# H32R10.net
KiCad netlist of a schematic drawn in EAGLE
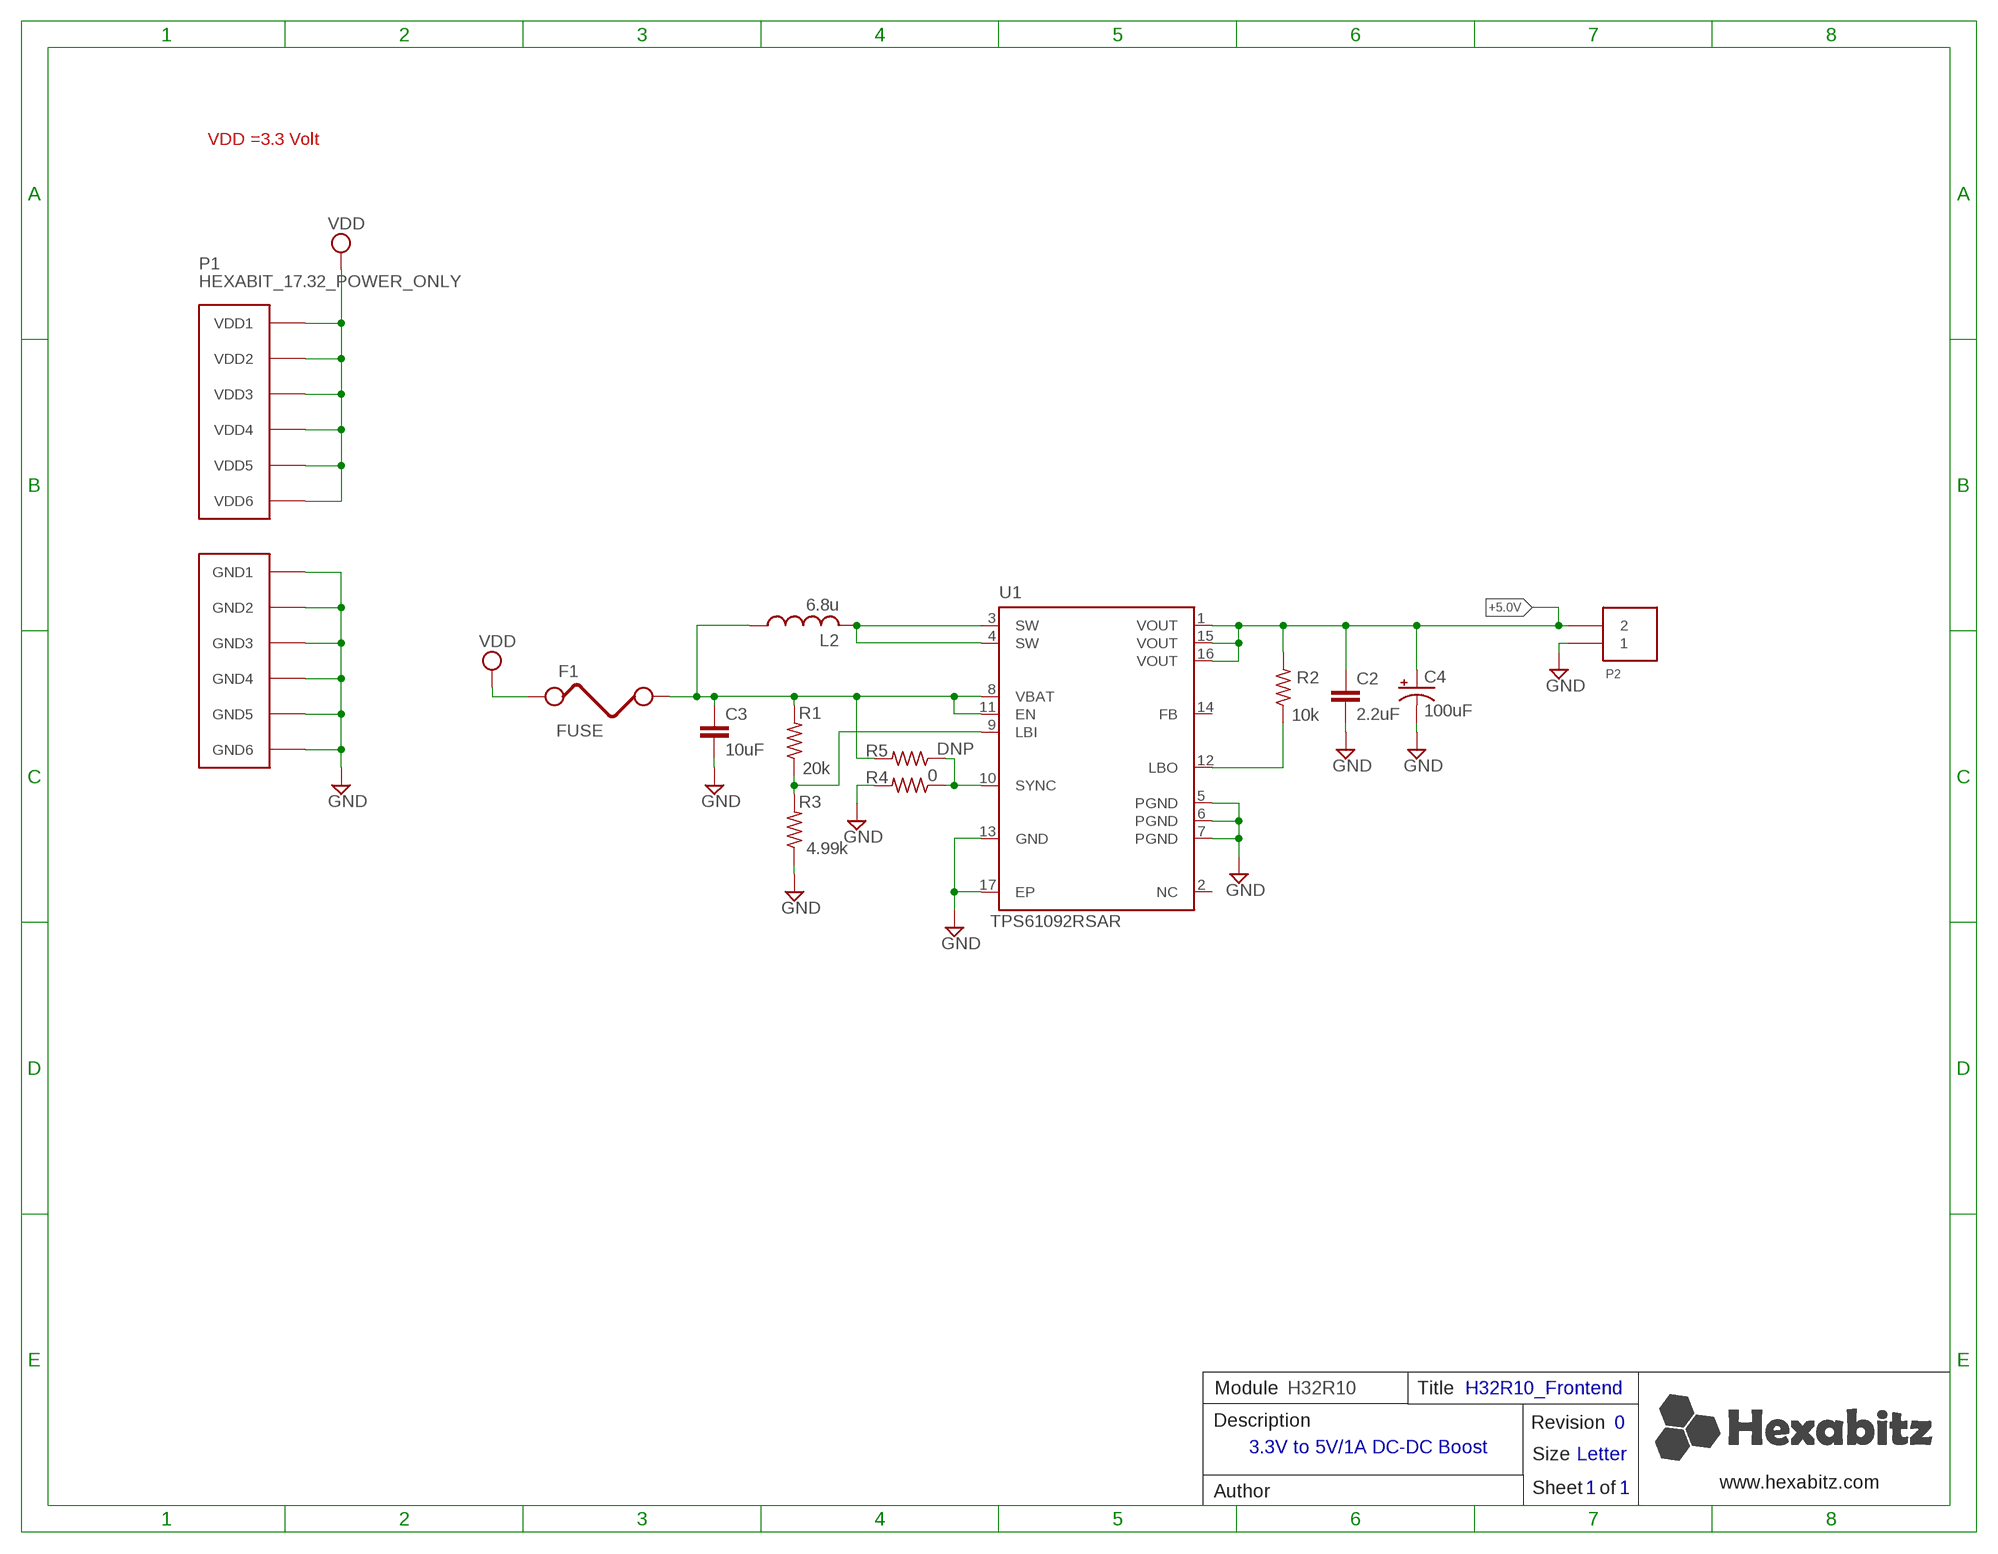
[diagram p0: schematic, sheet 1]

(export (version "E")
  (design (tool "Eeschema 10.0.6"))
  (components
    (comp (ref "C2")
      (value "2.2uF")
      (footprint "eagle-import:C-0603")
      (fields
        (field (name "CAPACITANCE") "2.2uF")
        (field (name "MFN") "TDK Corporation")
        (field (name "MPN") "C1608X5R1C225K080AB")
        (field (name "OCTOPART_URL") "https://octopart.com/search?q=C1608X5R1C225K080AB&start=0")
        (field (name "TOLERANCE") "±10%")
        (field (name "VOLTAGE_RATING") "16V")
      )
      (libsource (lib "eagle-import") (part "C-0603"))
    )
    (comp (ref "C3")
      (value "10uF")
      (footprint "eagle-import:C-0603")
      (fields
        (field (name "CAPACITANCE") "10uF")
        (field (name "MFN") "Murata")
        (field (name "MPN") "GRM188R60J106ME84D")
        (field (name "OCTOPART_URL") "https://octopart.com/search?r=sp&s=3UultoWHTYKlRdSTI8cSeA&q=GRM188R60J106ME84&start=0")
        (field (name "TOLERANCE") "±20%")
        (field (name "VOLTAGE_RATING") "6.3V")
      )
      (libsource (lib "eagle-import") (part "C-0603"))
    )
    (comp (ref "C4")
      (value "100uF")
      (footprint "eagle-import:C-1210-POL")
      (fields
        (field (name "CAPACITANCE") "100uF")
        (field (name "MFN") "Taiyo Yuden")
        (field (name "MPN") "LMK325ABJ107MMHT")
        (field (name "OCTOPART_URL") "https://octopart.com/search?q=LMK325ABJ107MMHT&start=0")
      )
      (libsource (lib "eagle-import") (part "C-1210-POL"))
    )
    (comp (ref "F1")
      (value "FUSE")
      (footprint "eagle-import:FUSE")
      (fields (field (name "MPN") "MINISMDC260F/16-2"))
      (libsource (lib "eagle-import") (part "FUSE"))
    )
    (comp (ref "L2")
      (value "6.8u")
      (footprint "eagle-import:IND-7447789006")
      (fields (field (name "MPN") "7447789006"))
      (libsource (lib "eagle-import") (part "IND-7447789006"))
    )
    (comp (ref "P1")
      (value "HEXABIT_17.32_POWER_ONLY")
      (footprint "eagle-import:HEXABIT_17.32_POWER_ONLY")
      (libsource (lib "eagle-import") (part "HEXABIT_?_POWER_ONLY17.32"))
    )
    (comp (ref "P2")
      (value "691311500102")
      (footprint "eagle-import:691311500102")
      (fields (field (name "MPN") "Wurth Electronics Inc."))
      (libsource (lib "eagle-import") (part "691311500102"))
    )
    (comp (ref "R1")
      (value "20k")
      (footprint "eagle-import:R-0402")
      (fields
        (field (name "MFN") "Yageo")
        (field (name "MPN") "RC0402FR-0720KL")
        (field (name "OCTOPART_URL") "https://octopart.com/search?q=%09%20RC0402FR-0720KL&start=0")
        (field (name "RESISTANCE") "20K")
        (field (name "TOLERANCE") "1%")
      )
      (libsource (lib "eagle-import") (part "R-0402"))
    )
    (comp (ref "R2")
      (value "10k")
      (footprint "eagle-import:R-0402")
      (fields
        (field (name "MFN") "Yageo")
        (field (name "MPN") "AT0402FRE0710KL")
        (field (name "OCTOPART_URL") "https://octopart.com/search?q=AT0402FRE0710KL&start=0")
        (field (name "RESISTANCE") "10K")
        (field (name "TOLERANCE") "1%")
      )
      (libsource (lib "eagle-import") (part "R-0402"))
    )
    (comp (ref "R3")
      (value "4.99k")
      (footprint "eagle-import:R-0402")
      (fields
        (field (name "MFN") "Yageo")
        (field (name "MPN") "AC0402FR-074K99L")
        (field (name "OCTOPART_URL") "https://octopart.com/search?q=AC0402FR-074K99L&start=0")
        (field (name "RESISTANCE") "4.99K")
        (field (name "TOLERANCE") "1%")
      )
      (libsource (lib "eagle-import") (part "R-0402"))
    )
    (comp (ref "R4")
      (value "0")
      (footprint "eagle-import:R-0402")
      (fields
        (field (name "MFN") "Yageo")
        (field (name "MPN") "AC0402JR-070RL")
        (field (name "OCTOPART_URL") "https://octopart.com/search?q=AC0402JR-070RL&start=0")
        (field (name "RESISTANCE") "0")
      )
      (libsource (lib "eagle-import") (part "R-0402"))
    )
    (comp (ref "R5")
      (value "DNP")
      (footprint "eagle-import:R-0402")
      (fields (field (name "MPN") "DNP"))
      (libsource (lib "eagle-import") (part "R-0402"))
    )
    (comp (ref "U1")
      (value "TPS61092RSAR")
      (footprint "eagle-import:TPS61092RSAR")
      (libsource (lib "eagle-import") (part "TPS61092RSAR"))
    )
  )
  (nets
    (net (code "1") (name "+5.0V") (class "Default")
      (node (ref "C2") (pin "1") (pinfunction "1_1") (pintype "passive"))
      (node (ref "C4") (pin "1") (pinfunction "+_1") (pintype "passive"))
      (node (ref "P2") (pin "2") (pinfunction "2_2") (pintype "power_in"))
      (node (ref "R2") (pin "2") (pinfunction "2_2") (pintype "passive"))
      (node (ref "U1") (pin "1") (pinfunction "VOUT_1") (pintype "bidirectional"))
      (node (ref "U1") (pin "15") (pinfunction "VOUT_15") (pintype "bidirectional"))
      (node (ref "U1") (pin "16") (pinfunction "VOUT_16") (pintype "bidirectional"))
    )
    (net (code "2") (name "GND") (class "Default")
      (node (ref "C2") (pin "2") (pinfunction "2_2") (pintype "passive"))
      (node (ref "C3") (pin "2") (pinfunction "2_2") (pintype "passive"))
      (node (ref "C4") (pin "2") (pinfunction "-_2") (pintype "passive"))
      (node (ref "P1") (pin "PAD_PD10") (pinfunction "GND4_PAD_PD10") (pintype "power_in"))
      (node (ref "P1") (pin "PAD_PD11") (pinfunction "GND5_PAD_PD11") (pintype "power_in"))
      (node (ref "P1") (pin "PAD_PD12") (pinfunction "GND6_PAD_PD12") (pintype "power_in"))
      (node (ref "P1") (pin "PAD_PD7") (pinfunction "GND1_PAD_PD7") (pintype "power_in"))
      (node (ref "P1") (pin "PAD_PD8") (pinfunction "GND2_PAD_PD8") (pintype "power_in"))
      (node (ref "P1") (pin "PAD_PD9") (pinfunction "GND3_PAD_PD9") (pintype "power_in"))
      (node (ref "P2") (pin "1") (pinfunction "1_1") (pintype "power_in"))
      (node (ref "R3") (pin "1") (pinfunction "1_1") (pintype "passive"))
      (node (ref "R4") (pin "2") (pinfunction "2_2") (pintype "passive"))
      (node (ref "U1") (pin "13") (pinfunction "GND_13") (pintype "bidirectional"))
      (node (ref "U1") (pin "17") (pinfunction "EP_17") (pintype "bidirectional"))
      (node (ref "U1") (pin "5") (pinfunction "PGND_5") (pintype "bidirectional"))
      (node (ref "U1") (pin "6") (pinfunction "PGND_6") (pintype "bidirectional"))
      (node (ref "U1") (pin "7") (pinfunction "PGND_7") (pintype "bidirectional"))
    )
    (net (code "3") (name "Net-(F1-P$2)") (class "Default")
      (node (ref "C3") (pin "1") (pinfunction "1_1") (pintype "passive"))
      (node (ref "F1") (pin "2") (pinfunction "P$2_2") (pintype "bidirectional"))
      (node (ref "L2") (pin "1") (pinfunction "1_1") (pintype "passive"))
      (node (ref "R1") (pin "2") (pinfunction "2_2") (pintype "passive"))
      (node (ref "R5") (pin "2") (pinfunction "2_2") (pintype "passive"))
      (node (ref "U1") (pin "11") (pinfunction "EN_11") (pintype "bidirectional"))
      (node (ref "U1") (pin "8") (pinfunction "VBAT_8") (pintype "bidirectional"))
    )
    (net (code "4") (name "Net-(L2-Pad2)") (class "Default")
      (node (ref "L2") (pin "2") (pinfunction "2_2") (pintype "passive"))
      (node (ref "U1") (pin "3") (pinfunction "SW_3") (pintype "bidirectional"))
      (node (ref "U1") (pin "4") (pinfunction "SW_4") (pintype "bidirectional"))
    )
    (net (code "5") (name "Net-(U1-LBI)") (class "Default")
      (node (ref "R1") (pin "1") (pinfunction "1_1") (pintype "passive"))
      (node (ref "R3") (pin "2") (pinfunction "2_2") (pintype "passive"))
      (node (ref "U1") (pin "9") (pinfunction "LBI_9") (pintype "bidirectional"))
    )
    (net (code "6") (name "Net-(U1-LBO)") (class "Default")
      (node (ref "R2") (pin "1") (pinfunction "1_1") (pintype "passive"))
      (node (ref "U1") (pin "12") (pinfunction "LBO_12") (pintype "bidirectional"))
    )
    (net (code "7") (name "Net-(U1-SYNC)") (class "Default")
      (node (ref "R4") (pin "1") (pinfunction "1_1") (pintype "passive"))
      (node (ref "R5") (pin "1") (pinfunction "1_1") (pintype "passive"))
      (node (ref "U1") (pin "10") (pinfunction "SYNC_10") (pintype "bidirectional"))
    )
    (net (code "8") (name "VDD") (class "Default")
      (node (ref "F1") (pin "1") (pinfunction "P$1_1") (pintype "bidirectional"))
      (node (ref "P1") (pin "PAD_PU10") (pinfunction "VDD4_PAD_PU10") (pintype "power_in"))
      (node (ref "P1") (pin "PAD_PU11") (pinfunction "VDD5_PAD_PU11") (pintype "power_in"))
      (node (ref "P1") (pin "PAD_PU12") (pinfunction "VDD6_PAD_PU12") (pintype "power_in"))
      (node (ref "P1") (pin "PAD_PU7") (pinfunction "VDD1_PAD_PU7") (pintype "power_in"))
      (node (ref "P1") (pin "PAD_PU8") (pinfunction "VDD2_PAD_PU8") (pintype "power_in"))
      (node (ref "P1") (pin "PAD_PU9") (pinfunction "VDD3_PAD_PU9") (pintype "power_in"))
    )
    (net (code "9") (name "unconnected-(U1-FB-Pad14)") (class "Default")
      (node (ref "U1") (pin "14") (pinfunction "FB_14") (pintype "bidirectional"))
    )
    (net (code "10") (name "unconnected-(U1-NC-Pad2)") (class "Default")
      (node (ref "U1") (pin "2") (pinfunction "NC_2") (pintype "bidirectional"))
    )
  )
)
